# VGA.net
KiCad netlist of a schematic drawn in Altium Designer
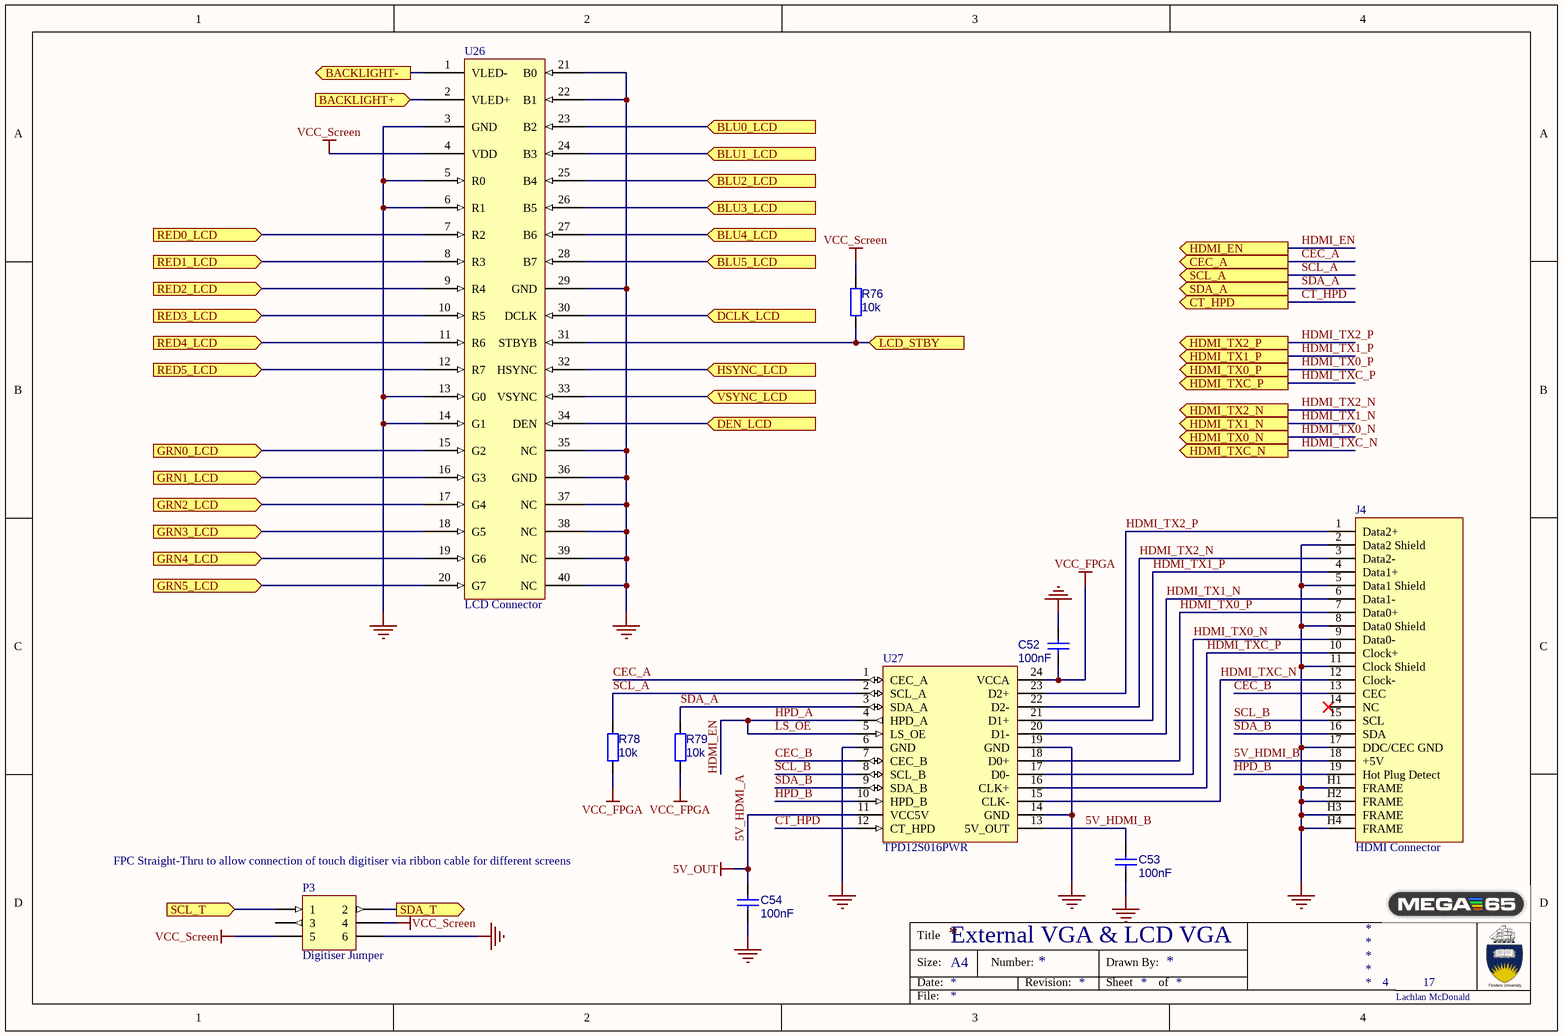
[diagram p0: VGA.SchDoc]

(export (version "E")
  (design (tool "Eeschema 10.0.6"))
  (components
    (comp (ref "C52")
      (value "100nF")
      (footprint "0603_CAP UF HD")
      (description "Capacitor")
      (libsource (lib "Workshop Library 2010_06_24") (part "Cap"))
    )
    (comp (ref "C53")
      (value "100nF")
      (footprint "0603_CAP UF HD")
      (description "Capacitor")
      (libsource (lib "Workshop Library 2010_06_24") (part "Cap"))
    )
    (comp (ref "C54")
      (value "100nF")
      (footprint "0603_CAP UF HD")
      (description "Capacitor")
      (libsource (lib "Workshop Library 2010_06_24") (part "Cap"))
    )
    (comp (ref "J4")
      (value "HDMI Connector")
      (footprint "A35071TR-ND")
      (description "HDMI Buchse 19Pol. 90°")
      (libsource (lib "TE0765") (part "HDMI"))
    )
    (comp (ref "P3")
      (value "Digitiser Jumper")
      (footprint "CONNECTOR FPC MOLEX 51281-0694")
      (description "Header, 3-Pin, Dual row")
      (fields (field (name "ELEMENT 14 PART NUMBER") "1324538") (field (name "MANUFACTURER") "Hirose"))
      (libsource (lib "MEGAphone") (part "Header 3X2"))
    )
    (comp (ref "R76")
      (value "10k")
      (footprint "0603-RESISTOR HD")
      (description "Resistor")
      (libsource (lib "MEGAphone") (part "Resistor"))
    )
    (comp (ref "R78")
      (value "10k")
      (footprint "0603-RESISTOR HD")
      (description "Resistor")
      (libsource (lib "MEGAphone") (part "Resistor"))
    )
    (comp (ref "R79")
      (value "10k")
      (footprint "0603-RESISTOR HD")
      (description "Resistor")
      (libsource (lib "MEGAphone") (part "Resistor"))
    )
    (comp (ref "U26")
      (value "LCD Connector")
      (footprint "Connector FPC 40 pin TE 4-1734839-0")
      (fields (field (name "ELEMENT 14 PART NUMBER") "1324569") (field (name "MANUFACTURER") "Hirose"))
      (libsource (lib "Schlib1") (part "LCD Connector"))
    )
    (comp (ref "U27")
      (value "TPD12S016PWR")
      (footprint "SOP65P640X120-24N")
      (libsource (lib "TE0765") (part "TPD12S016PWR"))
    )
  )
  (nets
    (net (code "1") (name "/5V_HDMI_B") (class "Default")
      (node (ref "C53") (pin "1") (pinfunction "1_1") (pintype "passive"))
      (node (ref "J4") (pin "18") (pinfunction "+5V_18") (pintype "passive"))
      (node (ref "U27") (pin "13") (pinfunction "5V_OUT_13") (pintype "power_in"))
    )
    (net (code "2") (name "/BACKLIGHT+") (class "Default")
      (node (ref "U26") (pin "2") (pinfunction "VLED+_2") (pintype "passive"))
    )
    (net (code "3") (name "/BACKLIGHT-") (class "Default")
      (node (ref "U26") (pin "1") (pinfunction "VLED-_1") (pintype "passive"))
    )
    (net (code "4") (name "/BLU0_LCD") (class "Default")
      (node (ref "U26") (pin "23") (pinfunction "B2_23") (pintype "input"))
    )
    (net (code "5") (name "/BLU1_LCD") (class "Default")
      (node (ref "U26") (pin "24") (pinfunction "B3_24") (pintype "input"))
    )
    (net (code "6") (name "/BLU2_LCD") (class "Default")
      (node (ref "U26") (pin "25") (pinfunction "B4_25") (pintype "input"))
    )
    (net (code "7") (name "/BLU3_LCD") (class "Default")
      (node (ref "U26") (pin "26") (pinfunction "B5_26") (pintype "input"))
    )
    (net (code "8") (name "/BLU4_LCD") (class "Default")
      (node (ref "U26") (pin "27") (pinfunction "B6_27") (pintype "input"))
    )
    (net (code "9") (name "/BLU5_LCD") (class "Default")
      (node (ref "U26") (pin "28") (pinfunction "B7_28") (pintype "input"))
    )
    (net (code "10") (name "/CEC_A") (class "Default")
      (node (ref "U27") (pin "1") (pinfunction "CEC_A_1") (pintype "bidirectional"))
    )
    (net (code "11") (name "/CEC_B") (class "Default")
      (node (ref "J4") (pin "13") (pinfunction "CEC_13") (pintype "passive"))
      (node (ref "U27") (pin "7") (pinfunction "CEC_B_7") (pintype "bidirectional"))
    )
    (net (code "12") (name "/CT_HPD") (class "Default")
      (node (ref "U27") (pin "12") (pinfunction "CT_HPD_12") (pintype "input"))
    )
    (net (code "13") (name "/DCLK_LCD") (class "Default")
      (node (ref "U26") (pin "30") (pinfunction "DCLK_30") (pintype "input"))
    )
    (net (code "14") (name "/DEN_LCD") (class "Default")
      (node (ref "U26") (pin "34") (pinfunction "DEN_34") (pintype "input"))
    )
    (net (code "15") (name "/GRN0_LCD") (class "Default")
      (node (ref "U26") (pin "15") (pinfunction "G2_15") (pintype "input"))
    )
    (net (code "16") (name "/GRN1_LCD") (class "Default")
      (node (ref "U26") (pin "16") (pinfunction "G3_16") (pintype "input"))
    )
    (net (code "17") (name "/GRN2_LCD") (class "Default")
      (node (ref "U26") (pin "17") (pinfunction "G4_17") (pintype "input"))
    )
    (net (code "18") (name "/GRN3_LCD") (class "Default")
      (node (ref "U26") (pin "18") (pinfunction "G5_18") (pintype "input"))
    )
    (net (code "19") (name "/GRN4_LCD") (class "Default")
      (node (ref "U26") (pin "19") (pinfunction "G6_19") (pintype "input"))
    )
    (net (code "20") (name "/GRN5_LCD") (class "Default")
      (node (ref "U26") (pin "20") (pinfunction "G7_20") (pintype "input"))
    )
    (net (code "21") (name "/HDMI_EN") (class "Default")
      (node (ref "U27") (pin "4") (pinfunction "HPD_A_4") (pintype "output"))
      (node (ref "U27") (pin "5") (pinfunction "LS_OE_5") (pintype "input"))
    )
    (net (code "22") (name "/HDMI_TX0_N") (class "Default")
      (node (ref "J4") (pin "9") (pinfunction "Data0-_9") (pintype "passive"))
      (node (ref "U27") (pin "17") (pinfunction "D0-_17") (pintype "passive"))
    )
    (net (code "23") (name "/HDMI_TX0_P") (class "Default")
      (node (ref "J4") (pin "7") (pinfunction "Data0+_7") (pintype "passive"))
      (node (ref "U27") (pin "18") (pinfunction "D0+_18") (pintype "passive"))
    )
    (net (code "24") (name "/HDMI_TX1_N") (class "Default")
      (node (ref "J4") (pin "6") (pinfunction "Data1-_6") (pintype "passive"))
      (node (ref "U27") (pin "20") (pinfunction "D1-_20") (pintype "passive"))
    )
    (net (code "25") (name "/HDMI_TX1_P") (class "Default")
      (node (ref "J4") (pin "4") (pinfunction "Data1+_4") (pintype "passive"))
      (node (ref "U27") (pin "21") (pinfunction "D1+_21") (pintype "passive"))
    )
    (net (code "26") (name "/HDMI_TX2_N") (class "Default")
      (node (ref "J4") (pin "3") (pinfunction "Data2-_3") (pintype "passive"))
      (node (ref "U27") (pin "22") (pinfunction "D2-_22") (pintype "passive"))
    )
    (net (code "27") (name "/HDMI_TX2_P") (class "Default")
      (node (ref "J4") (pin "1") (pinfunction "Data2+_1") (pintype "passive"))
      (node (ref "U27") (pin "23") (pinfunction "D2+_23") (pintype "passive"))
    )
    (net (code "28") (name "/HDMI_TXC_N") (class "Default")
      (node (ref "J4") (pin "12") (pinfunction "Clock-_12") (pintype "passive"))
      (node (ref "U27") (pin "15") (pinfunction "CLK-_15") (pintype "passive"))
    )
    (net (code "29") (name "/HDMI_TXC_P") (class "Default")
      (node (ref "J4") (pin "10") (pinfunction "Clock+_10") (pintype "passive"))
      (node (ref "U27") (pin "16") (pinfunction "CLK+_16") (pintype "passive"))
    )
    (net (code "30") (name "/HPD_B") (class "Default")
      (node (ref "J4") (pin "19") (pinfunction "Hot_Plug_Detect_19") (pintype "passive"))
      (node (ref "U27") (pin "10") (pinfunction "HPD_B_10") (pintype "input"))
    )
    (net (code "31") (name "/HSYNC_LCD") (class "Default")
      (node (ref "U26") (pin "32") (pinfunction "HSYNC_32") (pintype "input"))
    )
    (net (code "32") (name "/LCD_STBY") (class "Default")
      (node (ref "R76") (pin "2") (pinfunction "2_2") (pintype "passive"))
      (node (ref "U26") (pin "31") (pinfunction "STBYB_31") (pintype "input"))
    )
    (net (code "33") (name "/RED0_LCD") (class "Default")
      (node (ref "U26") (pin "7") (pinfunction "R2_7") (pintype "input"))
    )
    (net (code "34") (name "/RED1_LCD") (class "Default")
      (node (ref "U26") (pin "8") (pinfunction "R3_8") (pintype "input"))
    )
    (net (code "35") (name "/RED2_LCD") (class "Default")
      (node (ref "U26") (pin "9") (pinfunction "R4_9") (pintype "input"))
    )
    (net (code "36") (name "/RED3_LCD") (class "Default")
      (node (ref "U26") (pin "10") (pinfunction "R5_10") (pintype "input"))
    )
    (net (code "37") (name "/RED4_LCD") (class "Default")
      (node (ref "U26") (pin "11") (pinfunction "R6_11") (pintype "input"))
    )
    (net (code "38") (name "/RED5_LCD") (class "Default")
      (node (ref "U26") (pin "12") (pinfunction "R7_12") (pintype "input"))
    )
    (net (code "39") (name "/SCL_A") (class "Default")
      (node (ref "R78") (pin "1") (pinfunction "1_1") (pintype "passive"))
      (node (ref "U27") (pin "2") (pinfunction "SCL_A_2") (pintype "bidirectional"))
    )
    (net (code "40") (name "/SCL_B") (class "Default")
      (node (ref "J4") (pin "15") (pinfunction "SCL_15") (pintype "passive"))
      (node (ref "U27") (pin "8") (pinfunction "SCL_B_8") (pintype "bidirectional"))
    )
    (net (code "41") (name "/SCL_T") (class "Default")
      (node (ref "P3") (pin "1") (pinfunction "1_1") (pintype "input"))
    )
    (net (code "42") (name "/SDA_A") (class "Default")
      (node (ref "R79") (pin "1") (pinfunction "1_1") (pintype "passive"))
      (node (ref "U27") (pin "3") (pinfunction "SDA_A_3") (pintype "bidirectional"))
    )
    (net (code "43") (name "/SDA_B") (class "Default")
      (node (ref "J4") (pin "16") (pinfunction "SDA_16") (pintype "passive"))
      (node (ref "U27") (pin "9") (pinfunction "SDA_B_9") (pintype "bidirectional"))
    )
    (net (code "44") (name "/SDA_T") (class "Default")
      (node (ref "P3") (pin "2") (pinfunction "2_2") (pintype "output"))
    )
    (net (code "45") (name "/VSYNC_LCD") (class "Default")
      (node (ref "U26") (pin "33") (pinfunction "VSYNC_33") (pintype "input"))
    )
    (net (code "46") (name "5V_OUT") (class "Default")
      (node (ref "C54") (pin "1") (pinfunction "1_1") (pintype "passive"))
      (node (ref "U27") (pin "11") (pinfunction "VCC5V_11") (pintype "power_in"))
    )
    (net (code "47") (name "GND") (class "Default")
      (node (ref "C52") (pin "1") (pinfunction "1_1") (pintype "passive"))
      (node (ref "C53") (pin "2") (pinfunction "2_2") (pintype "passive"))
      (node (ref "C54") (pin "2") (pinfunction "2_2") (pintype "passive"))
      (node (ref "J4") (pin "11") (pinfunction "Clock_Shield_11") (pintype "passive"))
      (node (ref "J4") (pin "17") (pinfunction "DDC/CEC_GND_17") (pintype "passive"))
      (node (ref "J4") (pin "2") (pinfunction "Data2_Shield_2") (pintype "passive"))
      (node (ref "J4") (pin "5") (pinfunction "Data1_Shield_5") (pintype "passive"))
      (node (ref "J4") (pin "8") (pinfunction "Data0_Shield_8") (pintype "passive"))
      (node (ref "J4") (pin "H1") (pinfunction "FRAME_H1") (pintype "passive"))
      (node (ref "J4") (pin "H2") (pinfunction "FRAME_H2") (pintype "passive"))
      (node (ref "J4") (pin "H3") (pinfunction "FRAME_H3") (pintype "passive"))
      (node (ref "J4") (pin "H4") (pinfunction "FRAME_H4") (pintype "passive"))
      (node (ref "P3") (pin "6") (pinfunction "6_6") (pintype "passive"))
      (node (ref "U26") (pin "13") (pinfunction "G0_13") (pintype "input"))
      (node (ref "U26") (pin "14") (pinfunction "G1_14") (pintype "input"))
      (node (ref "U26") (pin "21") (pinfunction "B0_21") (pintype "input"))
      (node (ref "U26") (pin "22") (pinfunction "B1_22") (pintype "input"))
      (node (ref "U26") (pin "29") (pinfunction "GND_29") (pintype "passive"))
      (node (ref "U26") (pin "3") (pinfunction "GND_3") (pintype "passive"))
      (node (ref "U26") (pin "35") (pinfunction "NC_35") (pintype "passive"))
      (node (ref "U26") (pin "36") (pinfunction "GND_36") (pintype "passive"))
      (node (ref "U26") (pin "37") (pinfunction "NC_37") (pintype "passive"))
      (node (ref "U26") (pin "38") (pinfunction "NC_38") (pintype "passive"))
      (node (ref "U26") (pin "39") (pinfunction "NC_39") (pintype "passive"))
      (node (ref "U26") (pin "40") (pinfunction "NC_40") (pintype "passive"))
      (node (ref "U26") (pin "5") (pinfunction "R0_5") (pintype "input"))
      (node (ref "U26") (pin "6") (pinfunction "R1_6") (pintype "input"))
      (node (ref "U27") (pin "14") (pinfunction "GND_14") (pintype "passive"))
      (node (ref "U27") (pin "19") (pinfunction "GND_19") (pintype "power_in"))
      (node (ref "U27") (pin "6") (pinfunction "GND_6") (pintype "power_in"))
    )
    (net (code "48") (name "VCC_FPGA") (class "Default")
      (node (ref "C52") (pin "2") (pinfunction "2_2") (pintype "passive"))
      (node (ref "R78") (pin "2") (pinfunction "2_2") (pintype "passive"))
      (node (ref "R79") (pin "2") (pinfunction "2_2") (pintype "passive"))
      (node (ref "U27") (pin "24") (pinfunction "VCCA_24") (pintype "power_in"))
    )
    (net (code "49") (name "VCC_Screen") (class "Default")
      (node (ref "P3") (pin "4") (pinfunction "4_4") (pintype "passive"))
      (node (ref "P3") (pin "5") (pinfunction "5_5") (pintype "power_in"))
      (node (ref "R76") (pin "1") (pinfunction "1_1") (pintype "passive"))
      (node (ref "U26") (pin "4") (pinfunction "VDD_4") (pintype "passive"))
    )
    (net (code "50") (name "unconnected-(J4-NC-Pad14)") (class "Default")
      (node (ref "J4") (pin "14") (pinfunction "NC_14") (pintype "passive+no_connect"))
    )
    (net (code "51") (name "unconnected-(P3-Pad3)") (class "Default")
      (node (ref "P3") (pin "3") (pinfunction "3_3") (pintype "output"))
    )
  )
)
